# sensor_only.net
KiCad netlist of a schematic drawn in EAGLE
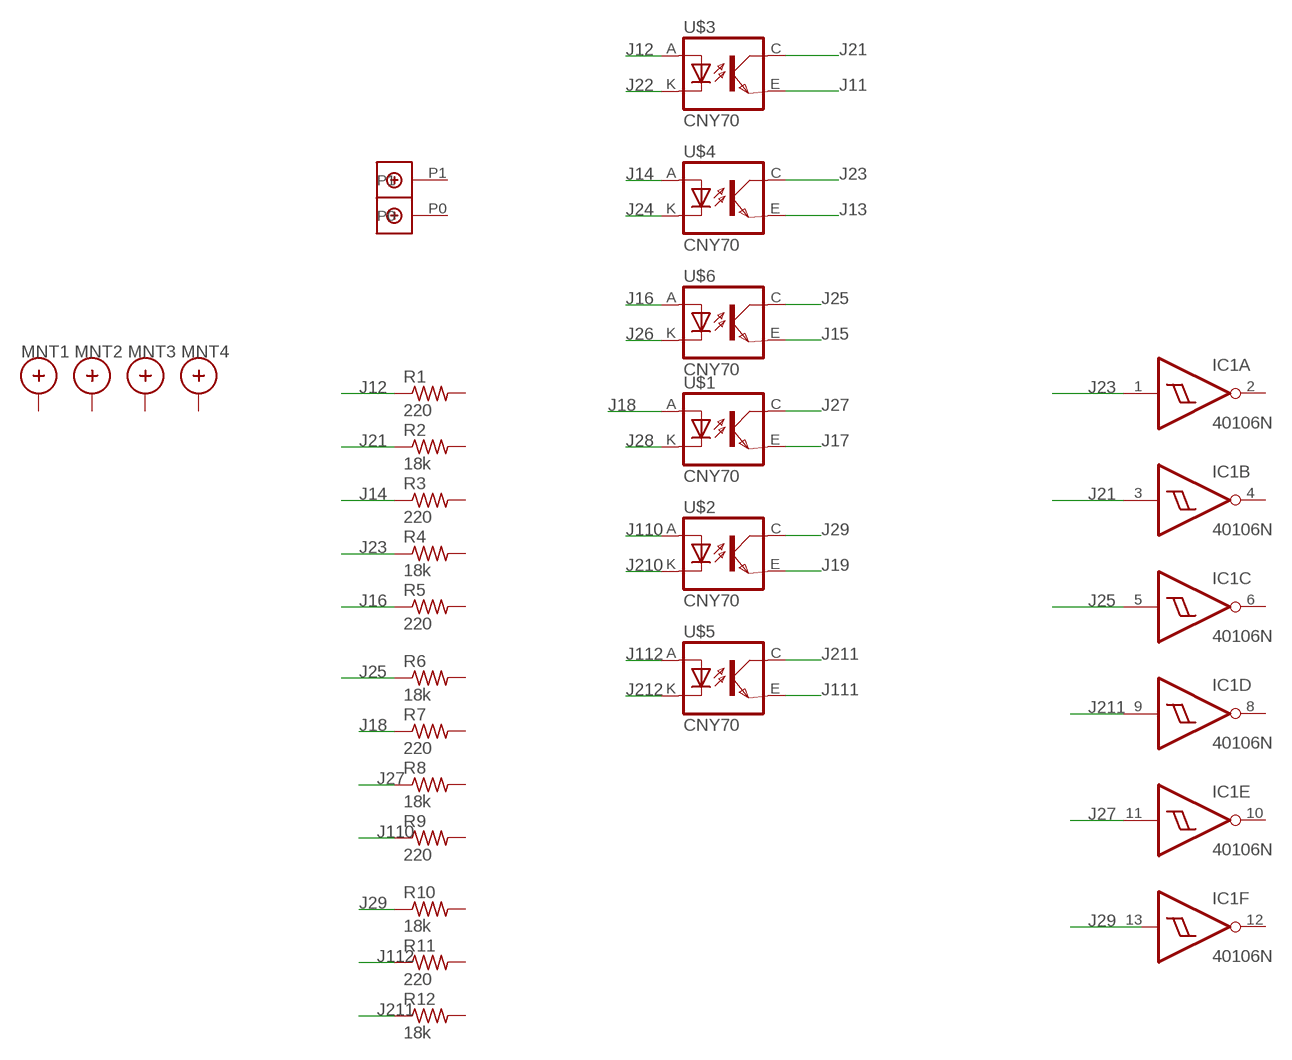
[diagram p0: schematic, sheet 1]

(export (version "E")
  (design (tool "Eeschema 10.0.6"))
  (components
    (comp (ref "IC1")
      (value "40106N")
      (footprint "eagle-import:DIL14")
      (libsource (lib "eagle-import") (part "40106N"))
    )
    (comp (ref "MNT1")
      (value "HOLE_MNT_0.135")
      (footprint "eagle-import:HOLE_MNT_#5-40")
      (libsource (lib "eagle-import") (part "HOLE_MNT_0.135"))
    )
    (comp (ref "MNT2")
      (value "HOLE_MNT_0.135")
      (footprint "eagle-import:HOLE_MNT_#5-40")
      (libsource (lib "eagle-import") (part "HOLE_MNT_0.135"))
    )
    (comp (ref "MNT3")
      (value "HOLE_MNT_0.135")
      (footprint "eagle-import:HOLE_MNT_#5-40")
      (libsource (lib "eagle-import") (part "HOLE_MNT_0.135"))
    )
    (comp (ref "MNT4")
      (value "HOLE_MNT_0.135")
      (footprint "eagle-import:HOLE_MNT_#5-40")
      (libsource (lib "eagle-import") (part "HOLE_MNT_0.135"))
    )
    (comp (ref "R1")
      (value "220")
      (footprint "eagle-import:0309_10")
      (libsource (lib "eagle-import") (part "R-US_0309/10"))
    )
    (comp (ref "R2")
      (value "18k")
      (footprint "eagle-import:0309_10")
      (libsource (lib "eagle-import") (part "R-US_0309/10"))
    )
    (comp (ref "R3")
      (value "220")
      (footprint "eagle-import:0309_10")
      (libsource (lib "eagle-import") (part "R-US_0309/10"))
    )
    (comp (ref "R4")
      (value "18k")
      (footprint "eagle-import:0309_10")
      (libsource (lib "eagle-import") (part "R-US_0309/10"))
    )
    (comp (ref "R5")
      (value "220")
      (footprint "eagle-import:0309_10")
      (libsource (lib "eagle-import") (part "R-US_0309/10"))
    )
    (comp (ref "R6")
      (value "18k")
      (footprint "eagle-import:0309_10")
      (libsource (lib "eagle-import") (part "R-US_0309/10"))
    )
    (comp (ref "R7")
      (value "220")
      (footprint "eagle-import:0309_10")
      (libsource (lib "eagle-import") (part "R-US_0309/10"))
    )
    (comp (ref "R8")
      (value "18k")
      (footprint "eagle-import:0309_10")
      (libsource (lib "eagle-import") (part "R-US_0309/10"))
    )
    (comp (ref "R9")
      (value "220")
      (footprint "eagle-import:0309_10")
      (libsource (lib "eagle-import") (part "R-US_0309/10"))
    )
    (comp (ref "R10")
      (value "18k")
      (footprint "eagle-import:0309_10")
      (libsource (lib "eagle-import") (part "R-US_0309/10"))
    )
    (comp (ref "R11")
      (value "220")
      (footprint "eagle-import:0309_10")
      (libsource (lib "eagle-import") (part "R-US_0309/10"))
    )
    (comp (ref "R12")
      (value "18k")
      (footprint "eagle-import:0309_10")
      (libsource (lib "eagle-import") (part "R-US_0309/10"))
    )
    (comp (ref "U$1")
      (value "CNY70")
      (footprint "eagle-import:4")
      (libsource (lib "eagle-import") (part "CNY70"))
    )
    (comp (ref "U$2")
      (value "CNY70")
      (footprint "eagle-import:4")
      (libsource (lib "eagle-import") (part "CNY70"))
    )
    (comp (ref "U$3")
      (value "CNY70")
      (footprint "eagle-import:4")
      (libsource (lib "eagle-import") (part "CNY70"))
    )
    (comp (ref "U$4")
      (value "CNY70")
      (footprint "eagle-import:4")
      (libsource (lib "eagle-import") (part "CNY70"))
    )
    (comp (ref "U$5")
      (value "CNY70")
      (footprint "eagle-import:4")
      (libsource (lib "eagle-import") (part "CNY70"))
    )
    (comp (ref "U$6")
      (value "CNY70")
      (footprint "eagle-import:4")
      (libsource (lib "eagle-import") (part "CNY70"))
    )
    (comp (ref "U$7")
      (value "DBCONN-1X2")
      (footprint "eagle-import:DBCONN-1X2")
      (libsource (lib "eagle-import") (part "DBCONN-1X2"))
    )
  )
  (nets
    (net (code "1") (name "/J11") (class "Default")
      (node (ref "U$3") (pin "E") (pinfunction "EMI_E") (pintype "passive"))
    )
    (net (code "2") (name "/J12") (class "Default")
      (node (ref "R1") (pin "1") (pinfunction "1_1") (pintype "passive"))
      (node (ref "U$3") (pin "A") (pinfunction "A_A") (pintype "passive"))
    )
    (net (code "3") (name "/J13") (class "Default")
      (node (ref "U$4") (pin "E") (pinfunction "EMI_E") (pintype "passive"))
    )
    (net (code "4") (name "/J14") (class "Default")
      (node (ref "R3") (pin "1") (pinfunction "1_1") (pintype "passive"))
      (node (ref "U$4") (pin "A") (pinfunction "A_A") (pintype "passive"))
    )
    (net (code "5") (name "/J15") (class "Default")
      (node (ref "U$6") (pin "E") (pinfunction "EMI_E") (pintype "passive"))
    )
    (net (code "6") (name "/J16") (class "Default")
      (node (ref "R5") (pin "1") (pinfunction "1_1") (pintype "passive"))
      (node (ref "U$6") (pin "A") (pinfunction "A_A") (pintype "passive"))
    )
    (net (code "7") (name "/J17") (class "Default")
      (node (ref "U$1") (pin "E") (pinfunction "EMI_E") (pintype "passive"))
    )
    (net (code "8") (name "/J18") (class "Default")
      (node (ref "R7") (pin "1") (pinfunction "1_1") (pintype "passive"))
      (node (ref "U$1") (pin "A") (pinfunction "A_A") (pintype "passive"))
    )
    (net (code "9") (name "/J19") (class "Default")
      (node (ref "U$2") (pin "E") (pinfunction "EMI_E") (pintype "passive"))
    )
    (net (code "10") (name "/J21") (class "Default")
      (node (ref "IC1") (pin "3") (pinfunction "I_3") (pintype "input"))
      (node (ref "R2") (pin "1") (pinfunction "1_1") (pintype "passive"))
      (node (ref "U$3") (pin "C") (pinfunction "COL_C") (pintype "passive"))
    )
    (net (code "11") (name "/J22") (class "Default")
      (node (ref "U$3") (pin "K") (pinfunction "C_K") (pintype "passive"))
    )
    (net (code "12") (name "/J23") (class "Default")
      (node (ref "IC1") (pin "1") (pinfunction "I_1") (pintype "input"))
      (node (ref "R4") (pin "1") (pinfunction "1_1") (pintype "passive"))
      (node (ref "U$4") (pin "C") (pinfunction "COL_C") (pintype "passive"))
    )
    (net (code "13") (name "/J24") (class "Default")
      (node (ref "U$4") (pin "K") (pinfunction "C_K") (pintype "passive"))
    )
    (net (code "14") (name "/J25") (class "Default")
      (node (ref "IC1") (pin "5") (pinfunction "I_5") (pintype "input"))
      (node (ref "R6") (pin "1") (pinfunction "1_1") (pintype "passive"))
      (node (ref "U$6") (pin "C") (pinfunction "COL_C") (pintype "passive"))
    )
    (net (code "15") (name "/J26") (class "Default")
      (node (ref "U$6") (pin "K") (pinfunction "C_K") (pintype "passive"))
    )
    (net (code "16") (name "/J27") (class "Default")
      (node (ref "IC1") (pin "11") (pinfunction "I_11") (pintype "input"))
      (node (ref "R8") (pin "1") (pinfunction "1_1") (pintype "passive"))
      (node (ref "U$1") (pin "C") (pinfunction "COL_C") (pintype "passive"))
    )
    (net (code "17") (name "/J28") (class "Default")
      (node (ref "U$1") (pin "K") (pinfunction "C_K") (pintype "passive"))
    )
    (net (code "18") (name "/J29") (class "Default")
      (node (ref "R10") (pin "1") (pinfunction "1_1") (pintype "passive"))
      (node (ref "U$2") (pin "C") (pinfunction "COL_C") (pintype "passive"))
    )
    (net (code "19") (name "/J110") (class "Default")
      (node (ref "R9") (pin "1") (pinfunction "1_1") (pintype "passive"))
      (node (ref "U$2") (pin "A") (pinfunction "A_A") (pintype "passive"))
    )
    (net (code "20") (name "/J111") (class "Default")
      (node (ref "U$5") (pin "E") (pinfunction "EMI_E") (pintype "passive"))
    )
    (net (code "21") (name "/J112") (class "Default")
      (node (ref "R11") (pin "1") (pinfunction "1_1") (pintype "passive"))
      (node (ref "U$5") (pin "A") (pinfunction "A_A") (pintype "passive"))
    )
    (net (code "22") (name "/J210") (class "Default")
      (node (ref "U$2") (pin "K") (pinfunction "C_K") (pintype "passive"))
    )
    (net (code "23") (name "/J211") (class "Default")
      (node (ref "IC1") (pin "9") (pinfunction "I_9") (pintype "input"))
      (node (ref "R12") (pin "1") (pinfunction "1_1") (pintype "passive"))
      (node (ref "U$5") (pin "C") (pinfunction "COL_C") (pintype "passive"))
    )
    (net (code "24") (name "/J212") (class "Default")
      (node (ref "U$5") (pin "K") (pinfunction "C_K") (pintype "passive"))
    )
    (net (code "25") (name "unconnected-(IC1A-O-Pad2)") (class "Default")
      (node (ref "IC1") (pin "2") (pinfunction "O_2") (pintype "output"))
    )
    (net (code "26") (name "unconnected-(IC1B-O-Pad4)") (class "Default")
      (node (ref "IC1") (pin "4") (pinfunction "O_4") (pintype "output"))
    )
    (net (code "27") (name "unconnected-(IC1C-O-Pad6)") (class "Default")
      (node (ref "IC1") (pin "6") (pinfunction "O_6") (pintype "output"))
    )
    (net (code "28") (name "unconnected-(IC1D-O-Pad8)") (class "Default")
      (node (ref "IC1") (pin "8") (pinfunction "O_8") (pintype "output"))
    )
    (net (code "29") (name "unconnected-(IC1E-O-Pad10)") (class "Default")
      (node (ref "IC1") (pin "10") (pinfunction "O_10") (pintype "output"))
    )
    (net (code "30") (name "unconnected-(IC1F-I-Pad13)") (class "Default")
      (node (ref "IC1") (pin "13") (pinfunction "I_13") (pintype "input"))
    )
    (net (code "31") (name "unconnected-(IC1F-O-Pad12)") (class "Default")
      (node (ref "IC1") (pin "12") (pinfunction "O_12") (pintype "output"))
    )
    (net (code "32") (name "unconnected-(MNT1-1-PadP$1)") (class "Default")
      (node (ref "MNT1") (pin "P$1") (pinfunction "1_P$1") (pintype "bidirectional"))
    )
    (net (code "33") (name "unconnected-(MNT2-1-PadP$1)") (class "Default")
      (node (ref "MNT2") (pin "P$1") (pinfunction "1_P$1") (pintype "bidirectional"))
    )
    (net (code "34") (name "unconnected-(MNT3-1-PadP$1)") (class "Default")
      (node (ref "MNT3") (pin "P$1") (pinfunction "1_P$1") (pintype "bidirectional"))
    )
    (net (code "35") (name "unconnected-(MNT4-1-PadP$1)") (class "Default")
      (node (ref "MNT4") (pin "P$1") (pinfunction "1_P$1") (pintype "bidirectional"))
    )
    (net (code "36") (name "unconnected-(R1-Pad2)") (class "Default")
      (node (ref "R1") (pin "2") (pinfunction "2_2") (pintype "passive"))
    )
    (net (code "37") (name "unconnected-(R2-Pad2)") (class "Default")
      (node (ref "R2") (pin "2") (pinfunction "2_2") (pintype "passive"))
    )
    (net (code "38") (name "unconnected-(R3-Pad2)") (class "Default")
      (node (ref "R3") (pin "2") (pinfunction "2_2") (pintype "passive"))
    )
    (net (code "39") (name "unconnected-(R4-Pad2)") (class "Default")
      (node (ref "R4") (pin "2") (pinfunction "2_2") (pintype "passive"))
    )
    (net (code "40") (name "unconnected-(R5-Pad2)") (class "Default")
      (node (ref "R5") (pin "2") (pinfunction "2_2") (pintype "passive"))
    )
    (net (code "41") (name "unconnected-(R6-Pad2)") (class "Default")
      (node (ref "R6") (pin "2") (pinfunction "2_2") (pintype "passive"))
    )
    (net (code "42") (name "unconnected-(R7-Pad2)") (class "Default")
      (node (ref "R7") (pin "2") (pinfunction "2_2") (pintype "passive"))
    )
    (net (code "43") (name "unconnected-(R8-Pad2)") (class "Default")
      (node (ref "R8") (pin "2") (pinfunction "2_2") (pintype "passive"))
    )
    (net (code "44") (name "unconnected-(R9-Pad2)") (class "Default")
      (node (ref "R9") (pin "2") (pinfunction "2_2") (pintype "passive"))
    )
    (net (code "45") (name "unconnected-(R10-Pad2)") (class "Default")
      (node (ref "R10") (pin "2") (pinfunction "2_2") (pintype "passive"))
    )
    (net (code "46") (name "unconnected-(R11-Pad2)") (class "Default")
      (node (ref "R11") (pin "2") (pinfunction "2_2") (pintype "passive"))
    )
    (net (code "47") (name "unconnected-(R12-Pad2)") (class "Default")
      (node (ref "R12") (pin "2") (pinfunction "2_2") (pintype "passive"))
    )
    (net (code "48") (name "unconnected-(U$7-PadP0)") (class "Default")
      (node (ref "U$7") (pin "P0") (pinfunction "P0_P0") (pintype "bidirectional"))
    )
    (net (code "49") (name "unconnected-(U$7-PadP1)") (class "Default")
      (node (ref "U$7") (pin "P1") (pinfunction "P1_P1") (pintype "bidirectional"))
    )
  )
)
